# Test_FRAM.net
KiCad netlist of a schematic drawn in EAGLE
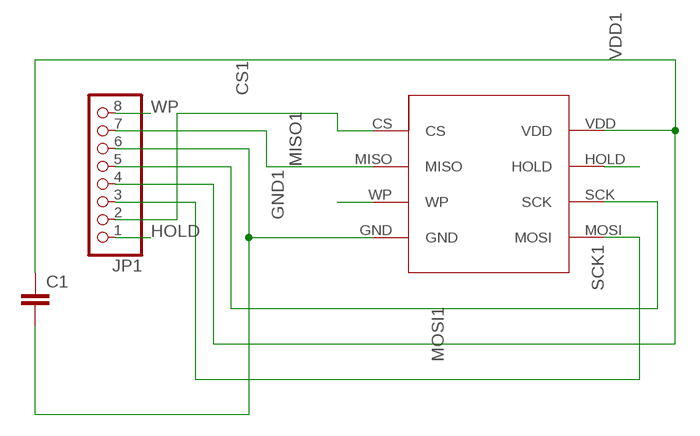
[diagram p0: schematic, sheet 1]

(export (version "E")
  (design (tool "Eeschema 10.0.6"))
  (components
    (comp (ref "C1")
      (value "C-EU025-040X050")
      (footprint "eagle-import:C025-040X050")
      (libsource (lib "eagle-import") (part "C-EU025-040X050"))
    )
    (comp (ref "JP1")
      (value "PINHD-1X8")
      (footprint "eagle-import:1X08")
      (libsource (lib "eagle-import") (part "PINHD-1X8"))
    )
    (comp (ref "U$1")
      (value "MB85RS")
      (footprint "eagle-import:SOIC8")
      (libsource (lib "eagle-import") (part "MB85RS"))
    )
  )
  (nets
    (net (code "1") (name "/CS1") (class "Default")
      (node (ref "JP1") (pin "2") (pinfunction "2_2") (pintype "passive"))
      (node (ref "U$1") (pin "CS") (pinfunction "CS_CS") (pintype "bidirectional"))
    )
    (net (code "2") (name "/GND1") (class "Default")
      (node (ref "C1") (pin "2") (pinfunction "2_2") (pintype "passive"))
      (node (ref "JP1") (pin "6") (pinfunction "6_6") (pintype "passive"))
      (node (ref "U$1") (pin "GND") (pinfunction "GND_GND") (pintype "bidirectional"))
    )
    (net (code "3") (name "/HOLD") (class "Default")
      (node (ref "JP1") (pin "1") (pinfunction "1_1") (pintype "passive"))
      (node (ref "U$1") (pin "HOLD") (pinfunction "HOLD_HOLD") (pintype "bidirectional"))
    )
    (net (code "4") (name "/MISO1") (class "Default")
      (node (ref "JP1") (pin "7") (pinfunction "7_7") (pintype "passive"))
      (node (ref "U$1") (pin "MISO") (pinfunction "MISO_MISO") (pintype "bidirectional"))
    )
    (net (code "5") (name "/MOSI1") (class "Default")
      (node (ref "JP1") (pin "3") (pinfunction "3_3") (pintype "passive"))
      (node (ref "U$1") (pin "MOSI") (pinfunction "MOSI_MOSI") (pintype "bidirectional"))
    )
    (net (code "6") (name "/SCK1") (class "Default")
      (node (ref "JP1") (pin "5") (pinfunction "5_5") (pintype "passive"))
      (node (ref "U$1") (pin "SCK") (pinfunction "SCK_SCK") (pintype "bidirectional"))
    )
    (net (code "7") (name "/VDD1") (class "Default")
      (node (ref "C1") (pin "1") (pinfunction "1_1") (pintype "passive"))
      (node (ref "JP1") (pin "4") (pinfunction "4_4") (pintype "passive"))
      (node (ref "U$1") (pin "VDD") (pinfunction "VDD_VDD") (pintype "bidirectional"))
    )
    (net (code "8") (name "/WP") (class "Default")
      (node (ref "JP1") (pin "8") (pinfunction "8_8") (pintype "passive"))
      (node (ref "U$1") (pin "WP") (pinfunction "WP_WP") (pintype "bidirectional"))
    )
  )
)
